# old_control_board.net
KiCad netlist of a schematic drawn in EAGLE
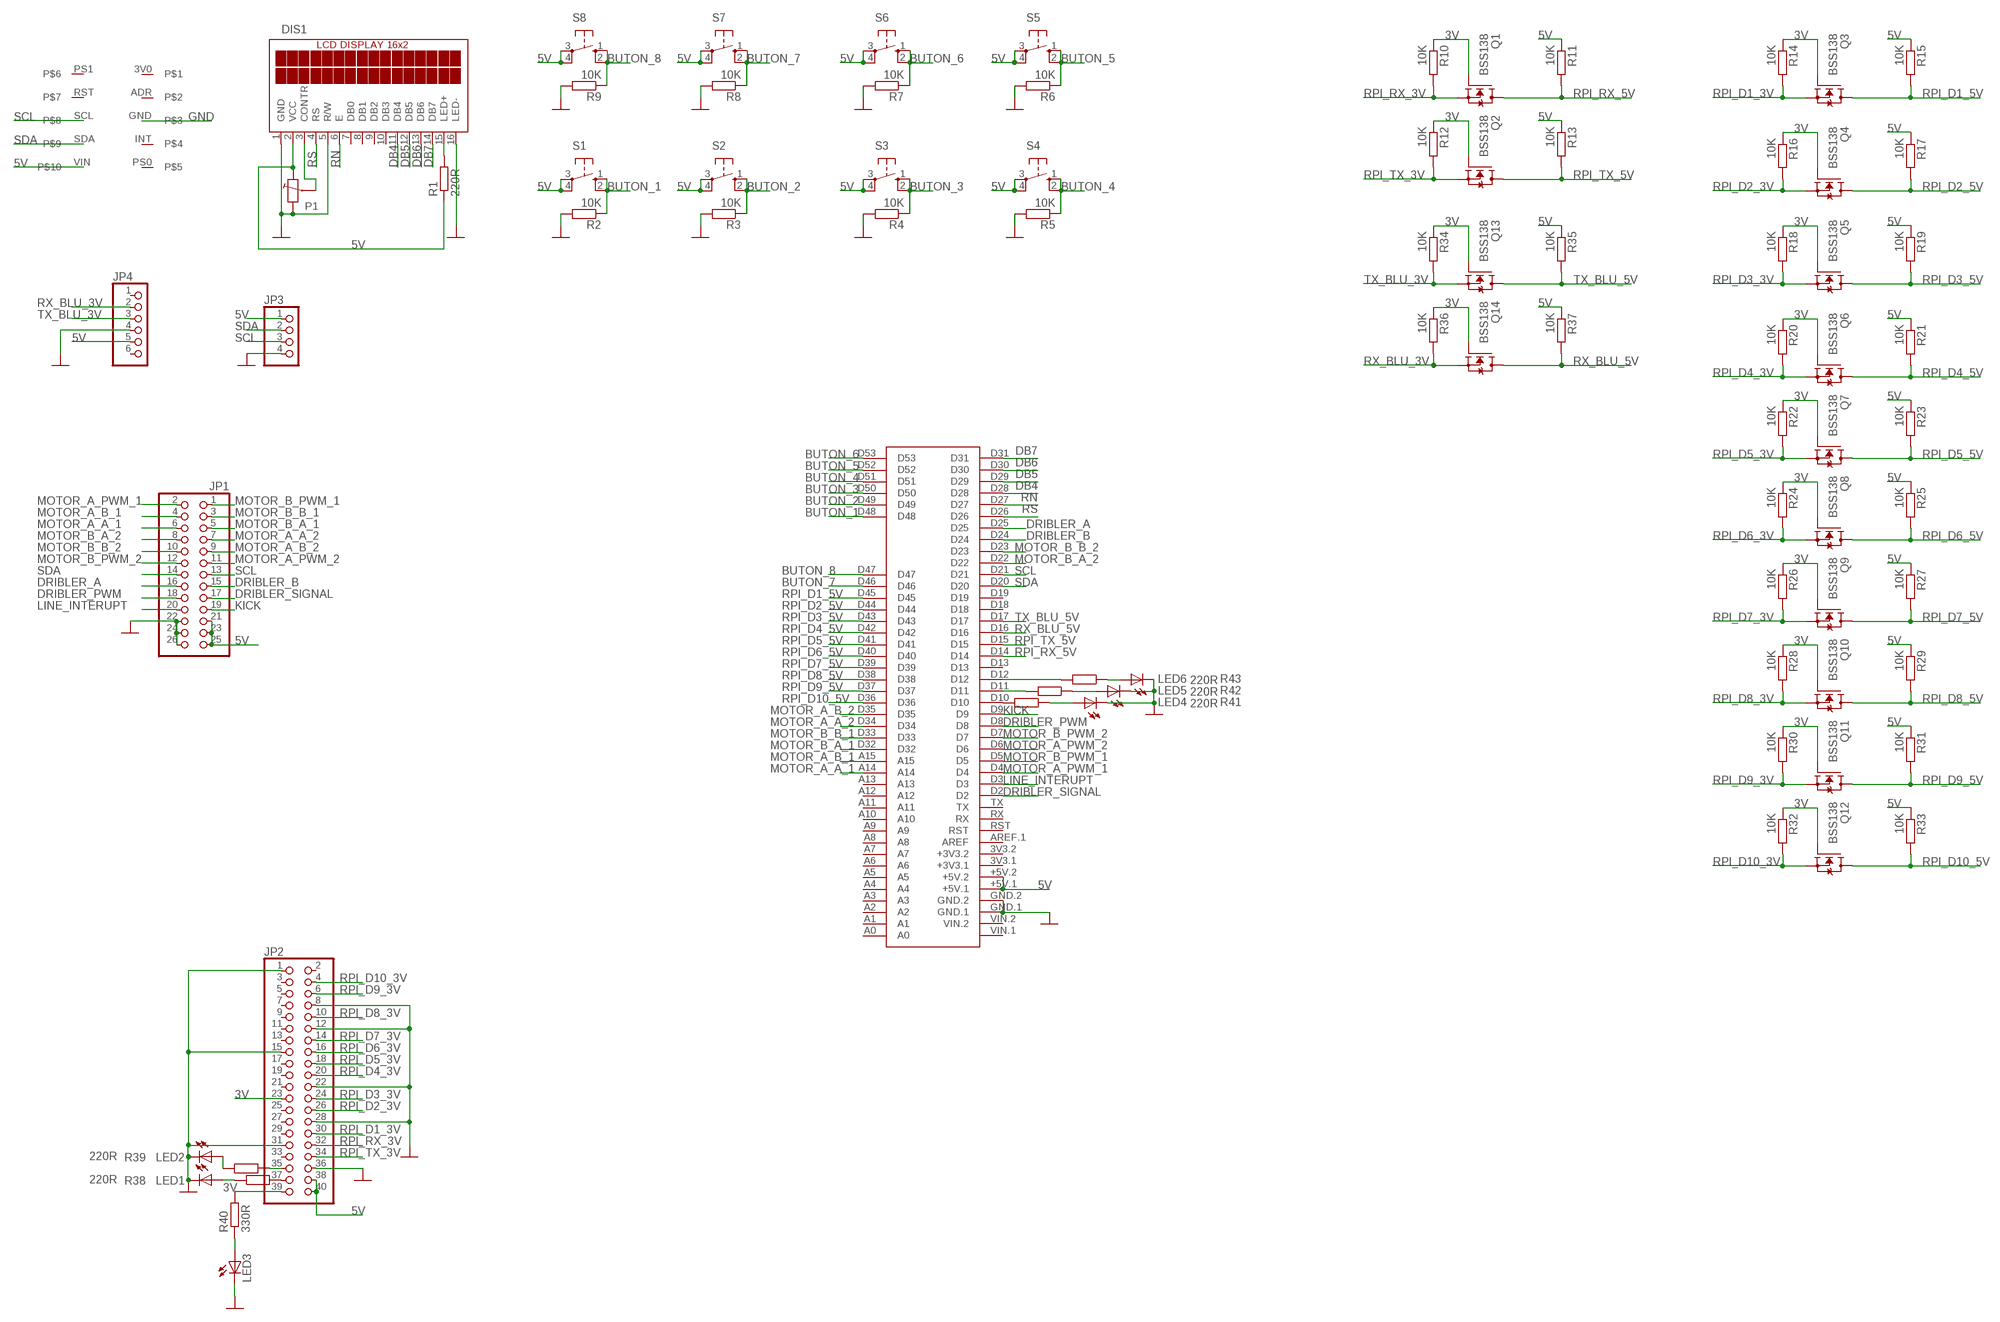
[diagram p0: schematic, sheet 1]

(export (version "E")
  (design (tool "Eeschema 10.0.6"))
  (components
    (comp (ref "DIS1")
      (value "LCD_DISPLEJ_16X2Z")
      (footprint "eagle-import:LCD_DISPLEJ_16X2")
      (libsource (lib "eagle-import") (part "LCD_DISPLEJ_16X2Z"))
    )
    (comp (ref "JP1")
      (value "PINHD-2X13_2.54")
      (footprint "eagle-import:2X13")
      (libsource (lib "eagle-import") (part "PINHD-2X13_2.54"))
    )
    (comp (ref "JP2")
      (value "PINHD-2X20_2.54")
      (footprint "eagle-import:2X20")
      (libsource (lib "eagle-import") (part "PINHD-2X20_2.54"))
    )
    (comp (ref "JP3")
      (value "PINHD-1X4_2.54")
      (footprint "eagle-import:1X04")
      (libsource (lib "eagle-import") (part "PINHD-1X4_2.54"))
    )
    (comp (ref "JP4")
      (value "PINHD-1X6_2.54")
      (footprint "eagle-import:1X06")
      (libsource (lib "eagle-import") (part "PINHD-1X6_2.54"))
    )
    (comp (ref "LED1")
      (value "LEDCHIPLED_0603")
      (footprint "eagle-import:CHIPLED_0603")
      (libsource (lib "eagle-import") (part "LEDCHIPLED_0603"))
    )
    (comp (ref "LED2")
      (value "LEDCHIPLED_0603")
      (footprint "eagle-import:CHIPLED_0603")
      (libsource (lib "eagle-import") (part "LEDCHIPLED_0603"))
    )
    (comp (ref "LED3")
      (value "LEDCHIPLED_0603")
      (footprint "eagle-import:CHIPLED_0603")
      (libsource (lib "eagle-import") (part "LEDCHIPLED_0603"))
    )
    (comp (ref "LED4")
      (value "LEDCHIPLED_0603")
      (footprint "eagle-import:CHIPLED_0603")
      (libsource (lib "eagle-import") (part "LEDCHIPLED_0603"))
    )
    (comp (ref "LED5")
      (value "LEDCHIPLED_0603")
      (footprint "eagle-import:CHIPLED_0603")
      (libsource (lib "eagle-import") (part "LEDCHIPLED_0603"))
    )
    (comp (ref "LED6")
      (value "LEDCHIPLED_0603")
      (footprint "eagle-import:CHIPLED_0603")
      (libsource (lib "eagle-import") (part "LEDCHIPLED_0603"))
    )
    (comp (ref "P1")
      (value "TRIMER-CA6V")
      (footprint "eagle-import:TP-CA6V")
      (libsource (lib "eagle-import") (part "TRIMER-CA6V"))
    )
    (comp (ref "Q1")
      (value "BSS138")
      (footprint "eagle-import:SOT23")
      (fields (field (name "MF") "Fairchild"))
      (libsource (lib "eagle-import") (part "BSS138"))
    )
    (comp (ref "Q2")
      (value "BSS138")
      (footprint "eagle-import:SOT23")
      (fields (field (name "MF") "Fairchild"))
      (libsource (lib "eagle-import") (part "BSS138"))
    )
    (comp (ref "Q3")
      (value "BSS138")
      (footprint "eagle-import:SOT23")
      (fields (field (name "MF") "Fairchild"))
      (libsource (lib "eagle-import") (part "BSS138"))
    )
    (comp (ref "Q4")
      (value "BSS138")
      (footprint "eagle-import:SOT23")
      (fields (field (name "MF") "Fairchild"))
      (libsource (lib "eagle-import") (part "BSS138"))
    )
    (comp (ref "Q5")
      (value "BSS138")
      (footprint "eagle-import:SOT23")
      (fields (field (name "MF") "Fairchild"))
      (libsource (lib "eagle-import") (part "BSS138"))
    )
    (comp (ref "Q6")
      (value "BSS138")
      (footprint "eagle-import:SOT23")
      (fields (field (name "MF") "Fairchild"))
      (libsource (lib "eagle-import") (part "BSS138"))
    )
    (comp (ref "Q7")
      (value "BSS138")
      (footprint "eagle-import:SOT23")
      (fields (field (name "MF") "Fairchild"))
      (libsource (lib "eagle-import") (part "BSS138"))
    )
    (comp (ref "Q8")
      (value "BSS138")
      (footprint "eagle-import:SOT23")
      (fields (field (name "MF") "Fairchild"))
      (libsource (lib "eagle-import") (part "BSS138"))
    )
    (comp (ref "Q9")
      (value "BSS138")
      (footprint "eagle-import:SOT23")
      (fields (field (name "MF") "Fairchild"))
      (libsource (lib "eagle-import") (part "BSS138"))
    )
    (comp (ref "Q10")
      (value "BSS138")
      (footprint "eagle-import:SOT23")
      (fields (field (name "MF") "Fairchild"))
      (libsource (lib "eagle-import") (part "BSS138"))
    )
    (comp (ref "Q11")
      (value "BSS138")
      (footprint "eagle-import:SOT23")
      (fields (field (name "MF") "Fairchild"))
      (libsource (lib "eagle-import") (part "BSS138"))
    )
    (comp (ref "Q12")
      (value "BSS138")
      (footprint "eagle-import:SOT23")
      (fields (field (name "MF") "Fairchild"))
      (libsource (lib "eagle-import") (part "BSS138"))
    )
    (comp (ref "Q13")
      (value "BSS138")
      (footprint "eagle-import:SOT23")
      (fields (field (name "MF") "Fairchild"))
      (libsource (lib "eagle-import") (part "BSS138"))
    )
    (comp (ref "Q14")
      (value "BSS138")
      (footprint "eagle-import:SOT23")
      (fields (field (name "MF") "Fairchild"))
      (libsource (lib "eagle-import") (part "BSS138"))
    )
    (comp (ref "R1")
      (value "220R")
      (footprint "eagle-import:R0603")
      (libsource (lib "eagle-import") (part "R-EU_R0603"))
    )
    (comp (ref "R2")
      (value "10K")
      (footprint "eagle-import:R0603")
      (libsource (lib "eagle-import") (part "R-EU_R0603"))
    )
    (comp (ref "R3")
      (value "10K")
      (footprint "eagle-import:R0603")
      (libsource (lib "eagle-import") (part "R-EU_R0603"))
    )
    (comp (ref "R4")
      (value "10K")
      (footprint "eagle-import:R0603")
      (libsource (lib "eagle-import") (part "R-EU_R0603"))
    )
    (comp (ref "R5")
      (value "10K")
      (footprint "eagle-import:R0603")
      (libsource (lib "eagle-import") (part "R-EU_R0603"))
    )
    (comp (ref "R6")
      (value "10K")
      (footprint "eagle-import:R0603")
      (libsource (lib "eagle-import") (part "R-EU_R0603"))
    )
    (comp (ref "R7")
      (value "10K")
      (footprint "eagle-import:R0603")
      (libsource (lib "eagle-import") (part "R-EU_R0603"))
    )
    (comp (ref "R8")
      (value "10K")
      (footprint "eagle-import:R0603")
      (libsource (lib "eagle-import") (part "R-EU_R0603"))
    )
    (comp (ref "R9")
      (value "10K")
      (footprint "eagle-import:R0603")
      (libsource (lib "eagle-import") (part "R-EU_R0603"))
    )
    (comp (ref "R10")
      (value "10K")
      (footprint "eagle-import:R0603")
      (libsource (lib "eagle-import") (part "R-EU_R0603"))
    )
    (comp (ref "R11")
      (value "10K")
      (footprint "eagle-import:R0603")
      (libsource (lib "eagle-import") (part "R-EU_R0603"))
    )
    (comp (ref "R12")
      (value "10K")
      (footprint "eagle-import:R0603")
      (libsource (lib "eagle-import") (part "R-EU_R0603"))
    )
    (comp (ref "R13")
      (value "10K")
      (footprint "eagle-import:R0603")
      (libsource (lib "eagle-import") (part "R-EU_R0603"))
    )
    (comp (ref "R14")
      (value "10K")
      (footprint "eagle-import:R0603")
      (libsource (lib "eagle-import") (part "R-EU_R0603"))
    )
    (comp (ref "R15")
      (value "10K")
      (footprint "eagle-import:R0603")
      (libsource (lib "eagle-import") (part "R-EU_R0603"))
    )
    (comp (ref "R16")
      (value "10K")
      (footprint "eagle-import:R0603")
      (libsource (lib "eagle-import") (part "R-EU_R0603"))
    )
    (comp (ref "R17")
      (value "10K")
      (footprint "eagle-import:R0603")
      (libsource (lib "eagle-import") (part "R-EU_R0603"))
    )
    (comp (ref "R18")
      (value "10K")
      (footprint "eagle-import:R0603")
      (libsource (lib "eagle-import") (part "R-EU_R0603"))
    )
    (comp (ref "R19")
      (value "10K")
      (footprint "eagle-import:R0603")
      (libsource (lib "eagle-import") (part "R-EU_R0603"))
    )
    (comp (ref "R20")
      (value "10K")
      (footprint "eagle-import:R0603")
      (libsource (lib "eagle-import") (part "R-EU_R0603"))
    )
    (comp (ref "R21")
      (value "10K")
      (footprint "eagle-import:R0603")
      (libsource (lib "eagle-import") (part "R-EU_R0603"))
    )
    (comp (ref "R22")
      (value "10K")
      (footprint "eagle-import:R0603")
      (libsource (lib "eagle-import") (part "R-EU_R0603"))
    )
    (comp (ref "R23")
      (value "10K")
      (footprint "eagle-import:R0603")
      (libsource (lib "eagle-import") (part "R-EU_R0603"))
    )
    (comp (ref "R24")
      (value "10K")
      (footprint "eagle-import:R0603")
      (libsource (lib "eagle-import") (part "R-EU_R0603"))
    )
    (comp (ref "R25")
      (value "10K")
      (footprint "eagle-import:R0603")
      (libsource (lib "eagle-import") (part "R-EU_R0603"))
    )
    (comp (ref "R26")
      (value "10K")
      (footprint "eagle-import:R0603")
      (libsource (lib "eagle-import") (part "R-EU_R0603"))
    )
    (comp (ref "R27")
      (value "10K")
      (footprint "eagle-import:R0603")
      (libsource (lib "eagle-import") (part "R-EU_R0603"))
    )
    (comp (ref "R28")
      (value "10K")
      (footprint "eagle-import:R0603")
      (libsource (lib "eagle-import") (part "R-EU_R0603"))
    )
    (comp (ref "R29")
      (value "10K")
      (footprint "eagle-import:R0603")
      (libsource (lib "eagle-import") (part "R-EU_R0603"))
    )
    (comp (ref "R30")
      (value "10K")
      (footprint "eagle-import:R0603")
      (libsource (lib "eagle-import") (part "R-EU_R0603"))
    )
    (comp (ref "R31")
      (value "10K")
      (footprint "eagle-import:R0603")
      (libsource (lib "eagle-import") (part "R-EU_R0603"))
    )
    (comp (ref "R32")
      (value "10K")
      (footprint "eagle-import:R0603")
      (libsource (lib "eagle-import") (part "R-EU_R0603"))
    )
    (comp (ref "R33")
      (value "10K")
      (footprint "eagle-import:R0603")
      (libsource (lib "eagle-import") (part "R-EU_R0603"))
    )
    (comp (ref "R34")
      (value "10K")
      (footprint "eagle-import:R0603")
      (libsource (lib "eagle-import") (part "R-EU_R0603"))
    )
    (comp (ref "R35")
      (value "10K")
      (footprint "eagle-import:R0603")
      (libsource (lib "eagle-import") (part "R-EU_R0603"))
    )
    (comp (ref "R36")
      (value "10K")
      (footprint "eagle-import:R0603")
      (libsource (lib "eagle-import") (part "R-EU_R0603"))
    )
    (comp (ref "R37")
      (value "10K")
      (footprint "eagle-import:R0603")
      (libsource (lib "eagle-import") (part "R-EU_R0603"))
    )
    (comp (ref "R38")
      (value "220R")
      (footprint "eagle-import:R0603")
      (libsource (lib "eagle-import") (part "R-EU_R0603"))
    )
    (comp (ref "R39")
      (value "220R")
      (footprint "eagle-import:R0603")
      (libsource (lib "eagle-import") (part "R-EU_R0603"))
    )
    (comp (ref "R40")
      (value "330R")
      (footprint "eagle-import:R0603")
      (libsource (lib "eagle-import") (part "R-EU_R0603"))
    )
    (comp (ref "R41")
      (value "220R")
      (footprint "eagle-import:R0603")
      (libsource (lib "eagle-import") (part "R-EU_R0603"))
    )
    (comp (ref "R42")
      (value "220R")
      (footprint "eagle-import:R0603")
      (libsource (lib "eagle-import") (part "R-EU_R0603"))
    )
    (comp (ref "R43")
      (value "220R")
      (footprint "eagle-import:R0603")
      (libsource (lib "eagle-import") (part "R-EU_R0603"))
    )
    (comp (ref "S1")
      (value "10-XX")
      (footprint "eagle-import:B3F-10XX")
      (fields (field (name "MPN") "B3F-1000"))
      (libsource (lib "eagle-import") (part "10-XX"))
    )
    (comp (ref "S2")
      (value "10-XX")
      (footprint "eagle-import:B3F-10XX")
      (fields (field (name "MPN") "B3F-1000"))
      (libsource (lib "eagle-import") (part "10-XX"))
    )
    (comp (ref "S3")
      (value "10-XX")
      (footprint "eagle-import:B3F-10XX")
      (fields (field (name "MPN") "B3F-1000"))
      (libsource (lib "eagle-import") (part "10-XX"))
    )
    (comp (ref "S4")
      (value "10-XX")
      (footprint "eagle-import:B3F-10XX")
      (fields (field (name "MPN") "B3F-1000"))
      (libsource (lib "eagle-import") (part "10-XX"))
    )
    (comp (ref "S5")
      (value "10-XX")
      (footprint "eagle-import:B3F-10XX")
      (fields (field (name "MPN") "B3F-1000"))
      (libsource (lib "eagle-import") (part "10-XX"))
    )
    (comp (ref "S6")
      (value "10-XX")
      (footprint "eagle-import:B3F-10XX")
      (fields (field (name "MPN") "B3F-1000"))
      (libsource (lib "eagle-import") (part "10-XX"))
    )
    (comp (ref "S7")
      (value "10-XX")
      (footprint "eagle-import:B3F-10XX")
      (fields (field (name "MPN") "B3F-1000"))
      (libsource (lib "eagle-import") (part "10-XX"))
    )
    (comp (ref "S8")
      (value "10-XX")
      (footprint "eagle-import:B3F-10XX")
      (fields (field (name "MPN") "B3F-1000"))
      (libsource (lib "eagle-import") (part "10-XX"))
    )
    (comp (ref "U$1")
      (value "MEGA2560_MIKRO")
      (footprint "eagle-import:MEGA2560_MIKRO")
      (libsource (lib "eagle-import") (part "MEGA2560_MIKRO"))
    )
    (comp (ref "U$2")
      (value "BNO055")
      (footprint "eagle-import:BNO005")
      (libsource (lib "eagle-import") (part "BNO055"))
    )
  )
  (nets
    (net (code "1") (name "/3V") (class "Default")
      (node (ref "JP2") (pin "23") (pinfunction "23_23") (pintype "passive"))
      (node (ref "JP2") (pin "39") (pinfunction "39_39") (pintype "passive"))
      (node (ref "Q1") (pin "1") (pinfunction "G_1") (pintype "passive"))
      (node (ref "Q10") (pin "1") (pinfunction "G_1") (pintype "passive"))
      (node (ref "Q11") (pin "1") (pinfunction "G_1") (pintype "passive"))
      (node (ref "Q12") (pin "1") (pinfunction "G_1") (pintype "passive"))
      (node (ref "Q13") (pin "1") (pinfunction "G_1") (pintype "passive"))
      (node (ref "Q14") (pin "1") (pinfunction "G_1") (pintype "passive"))
      (node (ref "Q2") (pin "1") (pinfunction "G_1") (pintype "passive"))
      (node (ref "Q3") (pin "1") (pinfunction "G_1") (pintype "passive"))
      (node (ref "Q4") (pin "1") (pinfunction "G_1") (pintype "passive"))
      (node (ref "Q5") (pin "1") (pinfunction "G_1") (pintype "passive"))
      (node (ref "Q6") (pin "1") (pinfunction "G_1") (pintype "passive"))
      (node (ref "Q7") (pin "1") (pinfunction "G_1") (pintype "passive"))
      (node (ref "Q8") (pin "1") (pinfunction "G_1") (pintype "passive"))
      (node (ref "Q9") (pin "1") (pinfunction "G_1") (pintype "passive"))
      (node (ref "R10") (pin "1") (pinfunction "1_1") (pintype "passive"))
      (node (ref "R12") (pin "1") (pinfunction "1_1") (pintype "passive"))
      (node (ref "R14") (pin "1") (pinfunction "1_1") (pintype "passive"))
      (node (ref "R16") (pin "1") (pinfunction "1_1") (pintype "passive"))
      (node (ref "R18") (pin "1") (pinfunction "1_1") (pintype "passive"))
      (node (ref "R20") (pin "1") (pinfunction "1_1") (pintype "passive"))
      (node (ref "R22") (pin "1") (pinfunction "1_1") (pintype "passive"))
      (node (ref "R24") (pin "1") (pinfunction "1_1") (pintype "passive"))
      (node (ref "R26") (pin "1") (pinfunction "1_1") (pintype "passive"))
      (node (ref "R28") (pin "1") (pinfunction "1_1") (pintype "passive"))
      (node (ref "R30") (pin "1") (pinfunction "1_1") (pintype "passive"))
      (node (ref "R32") (pin "1") (pinfunction "1_1") (pintype "passive"))
      (node (ref "R34") (pin "1") (pinfunction "1_1") (pintype "passive"))
      (node (ref "R36") (pin "1") (pinfunction "1_1") (pintype "passive"))
      (node (ref "R40") (pin "2") (pinfunction "2_2") (pintype "passive"))
    )
    (net (code "2") (name "/5V") (class "Default")
      (node (ref "DIS1") (pin "2") (pinfunction "VCC_2") (pintype "power_in"))
      (node (ref "JP1") (pin "21") (pinfunction "21_21") (pintype "passive"))
      (node (ref "JP1") (pin "23") (pinfunction "23_23") (pintype "passive"))
      (node (ref "JP1") (pin "25") (pinfunction "25_25") (pintype "passive"))
      (node (ref "JP2") (pin "38") (pinfunction "38_38") (pintype "passive"))
      (node (ref "JP2") (pin "40") (pinfunction "40_40") (pintype "passive"))
      (node (ref "JP3") (pin "1") (pinfunction "1_1") (pintype "passive"))
      (node (ref "JP4") (pin "5") (pinfunction "5_5") (pintype "passive"))
      (node (ref "P1") (pin "2") (pinfunction "2_2") (pintype "passive"))
      (node (ref "R1") (pin "1") (pinfunction "1_1") (pintype "passive"))
      (node (ref "R11") (pin "1") (pinfunction "1_1") (pintype "passive"))
      (node (ref "R13") (pin "1") (pinfunction "1_1") (pintype "passive"))
      (node (ref "R15") (pin "1") (pinfunction "1_1") (pintype "passive"))
      (node (ref "R17") (pin "1") (pinfunction "1_1") (pintype "passive"))
      (node (ref "R19") (pin "1") (pinfunction "1_1") (pintype "passive"))
      (node (ref "R21") (pin "1") (pinfunction "1_1") (pintype "passive"))
      (node (ref "R23") (pin "1") (pinfunction "1_1") (pintype "passive"))
      (node (ref "R25") (pin "1") (pinfunction "1_1") (pintype "passive"))
      (node (ref "R27") (pin "1") (pinfunction "1_1") (pintype "passive"))
      (node (ref "R29") (pin "1") (pinfunction "1_1") (pintype "passive"))
      (node (ref "R31") (pin "1") (pinfunction "1_1") (pintype "passive"))
      (node (ref "R33") (pin "1") (pinfunction "1_1") (pintype "passive"))
      (node (ref "R35") (pin "1") (pinfunction "1_1") (pintype "passive"))
      (node (ref "R37") (pin "1") (pinfunction "1_1") (pintype "passive"))
      (node (ref "S1") (pin "3") (pinfunction "P_3") (pintype "passive"))
      (node (ref "S1") (pin "4") (pinfunction "P1_4") (pintype "passive"))
      (node (ref "S2") (pin "3") (pinfunction "P_3") (pintype "passive"))
      (node (ref "S2") (pin "4") (pinfunction "P1_4") (pintype "passive"))
      (node (ref "S3") (pin "3") (pinfunction "P_3") (pintype "passive"))
      (node (ref "S3") (pin "4") (pinfunction "P1_4") (pintype "passive"))
      (node (ref "S4") (pin "3") (pinfunction "P_3") (pintype "passive"))
      (node (ref "S4") (pin "4") (pinfunction "P1_4") (pintype "passive"))
      (node (ref "S5") (pin "3") (pinfunction "P_3") (pintype "passive"))
      (node (ref "S5") (pin "4") (pinfunction "P1_4") (pintype "passive"))
      (node (ref "S6") (pin "3") (pinfunction "P_3") (pintype "passive"))
      (node (ref "S6") (pin "4") (pinfunction "P1_4") (pintype "passive"))
      (node (ref "S7") (pin "3") (pinfunction "P_3") (pintype "passive"))
      (node (ref "S7") (pin "4") (pinfunction "P1_4") (pintype "passive"))
      (node (ref "S8") (pin "3") (pinfunction "P_3") (pintype "passive"))
      (node (ref "S8") (pin "4") (pinfunction "P1_4") (pintype "passive"))
      (node (ref "U$1") (pin "+5V.1") (pinfunction "+5V.1_+5V.1") (pintype "bidirectional"))
      (node (ref "U$1") (pin "+5V.2") (pinfunction "+5V.2_+5V.2") (pintype "bidirectional"))
      (node (ref "U$2") (pin "VIN") (pinfunction "P$10_VIN") (pintype "bidirectional"))
    )
    (net (code "3") (name "/BUTON_1") (class "Default")
      (node (ref "R2") (pin "1") (pinfunction "1_1") (pintype "passive"))
      (node (ref "S1") (pin "1") (pinfunction "S_1") (pintype "passive"))
      (node (ref "S1") (pin "2") (pinfunction "S1_2") (pintype "passive"))
      (node (ref "U$1") (pin "D48") (pinfunction "D48_D48") (pintype "bidirectional"))
    )
    (net (code "4") (name "/BUTON_2") (class "Default")
      (node (ref "R3") (pin "1") (pinfunction "1_1") (pintype "passive"))
      (node (ref "S2") (pin "1") (pinfunction "S_1") (pintype "passive"))
      (node (ref "S2") (pin "2") (pinfunction "S1_2") (pintype "passive"))
      (node (ref "U$1") (pin "D49") (pinfunction "D49_D49") (pintype "bidirectional"))
    )
    (net (code "5") (name "/BUTON_3") (class "Default")
      (node (ref "R4") (pin "1") (pinfunction "1_1") (pintype "passive"))
      (node (ref "S3") (pin "1") (pinfunction "S_1") (pintype "passive"))
      (node (ref "S3") (pin "2") (pinfunction "S1_2") (pintype "passive"))
      (node (ref "U$1") (pin "D50") (pinfunction "D50_D50") (pintype "bidirectional"))
    )
    (net (code "6") (name "/BUTON_4") (class "Default")
      (node (ref "R5") (pin "1") (pinfunction "1_1") (pintype "passive"))
      (node (ref "S4") (pin "1") (pinfunction "S_1") (pintype "passive"))
      (node (ref "S4") (pin "2") (pinfunction "S1_2") (pintype "passive"))
      (node (ref "U$1") (pin "D51") (pinfunction "D51_D51") (pintype "bidirectional"))
    )
    (net (code "7") (name "/BUTON_5") (class "Default")
      (node (ref "R6") (pin "1") (pinfunction "1_1") (pintype "passive"))
      (node (ref "S5") (pin "1") (pinfunction "S_1") (pintype "passive"))
      (node (ref "S5") (pin "2") (pinfunction "S1_2") (pintype "passive"))
      (node (ref "U$1") (pin "D52") (pinfunction "D52_D52") (pintype "bidirectional"))
    )
    (net (code "8") (name "/BUTON_6") (class "Default")
      (node (ref "R7") (pin "1") (pinfunction "1_1") (pintype "passive"))
      (node (ref "S6") (pin "1") (pinfunction "S_1") (pintype "passive"))
      (node (ref "S6") (pin "2") (pinfunction "S1_2") (pintype "passive"))
      (node (ref "U$1") (pin "D53") (pinfunction "D53_D53") (pintype "bidirectional"))
    )
    (net (code "9") (name "/BUTON_7") (class "Default")
      (node (ref "R8") (pin "1") (pinfunction "1_1") (pintype "passive"))
      (node (ref "S7") (pin "1") (pinfunction "S_1") (pintype "passive"))
      (node (ref "S7") (pin "2") (pinfunction "S1_2") (pintype "passive"))
      (node (ref "U$1") (pin "D46") (pinfunction "D46_D46") (pintype "bidirectional"))
    )
    (net (code "10") (name "/BUTON_8") (class "Default")
      (node (ref "R9") (pin "1") (pinfunction "1_1") (pintype "passive"))
      (node (ref "S8") (pin "1") (pinfunction "S_1") (pintype "passive"))
      (node (ref "S8") (pin "2") (pinfunction "S1_2") (pintype "passive"))
      (node (ref "U$1") (pin "D47") (pinfunction "D47_D47") (pintype "bidirectional"))
    )
    (net (code "11") (name "/DB4") (class "Default")
      (node (ref "DIS1") (pin "11") (pinfunction "DB4_11") (pintype "bidirectional"))
      (node (ref "U$1") (pin "D28") (pinfunction "D28_D28") (pintype "bidirectional"))
    )
    (net (code "12") (name "/DB5") (class "Default")
      (node (ref "DIS1") (pin "12") (pinfunction "DB5_12") (pintype "bidirectional"))
      (node (ref "U$1") (pin "D29") (pinfunction "D29_D29") (pintype "bidirectional"))
    )
    (net (code "13") (name "/DB6") (class "Default")
      (node (ref "DIS1") (pin "13") (pinfunction "DB6_13") (pintype "bidirectional"))
      (node (ref "U$1") (pin "D30") (pinfunction "D30_D30") (pintype "bidirectional"))
    )
    (net (code "14") (name "/DB7") (class "Default")
      (node (ref "DIS1") (pin "14") (pinfunction "DB7_14") (pintype "bidirectional"))
      (node (ref "U$1") (pin "D31") (pinfunction "D31_D31") (pintype "bidirectional"))
    )
    (net (code "15") (name "/DRIBLER_A") (class "Default")
      (node (ref "JP1") (pin "16") (pinfunction "16_16") (pintype "passive"))
      (node (ref "U$1") (pin "D25") (pinfunction "D25_D25") (pintype "bidirectional"))
    )
    (net (code "16") (name "/DRIBLER_B") (class "Default")
      (node (ref "JP1") (pin "15") (pinfunction "15_15") (pintype "passive"))
      (node (ref "U$1") (pin "D24") (pinfunction "D24_D24") (pintype "bidirectional"))
    )
    (net (code "17") (name "/DRIBLER_PWM") (class "Default")
      (node (ref "JP1") (pin "18") (pinfunction "18_18") (pintype "passive"))
      (node (ref "U$1") (pin "D8") (pinfunction "D8_D8") (pintype "bidirectional"))
    )
    (net (code "18") (name "/DRIBLER_SIGNAL") (class "Default")
      (node (ref "JP1") (pin "17") (pinfunction "17_17") (pintype "passive"))
      (node (ref "U$1") (pin "D2") (pinfunction "D2_D2") (pintype "bidirectional"))
    )
    (net (code "19") (name "/KICK") (class "Default")
      (node (ref "JP1") (pin "19") (pinfunction "19_19") (pintype "passive"))
      (node (ref "U$1") (pin "D9") (pinfunction "D9_D9") (pintype "bidirectional"))
    )
    (net (code "20") (name "/LINE_INTERUPT") (class "Default")
      (node (ref "JP1") (pin "20") (pinfunction "20_20") (pintype "passive"))
      (node (ref "U$1") (pin "D3") (pinfunction "D3_D3") (pintype "bidirectional"))
    )
    (net (code "21") (name "/MOTOR_A_A_1") (class "Default")
      (node (ref "JP1") (pin "6") (pinfunction "6_6") (pintype "passive"))
      (node (ref "U$1") (pin "A14") (pinfunction "A14_A14") (pintype "bidirectional"))
    )
    (net (code "22") (name "/MOTOR_A_A_2") (class "Default")
      (node (ref "JP1") (pin "7") (pinfunction "7_7") (pintype "passive"))
      (node (ref "U$1") (pin "D34") (pinfunction "D34_D34") (pintype "bidirectional"))
    )
    (net (code "23") (name "/MOTOR_A_B_1") (class "Default")
      (node (ref "JP1") (pin "4") (pinfunction "4_4") (pintype "passive"))
      (node (ref "U$1") (pin "A15") (pinfunction "A15_A15") (pintype "bidirectional"))
    )
    (net (code "24") (name "/MOTOR_A_B_2") (class "Default")
      (node (ref "JP1") (pin "9") (pinfunction "9_9") (pintype "passive"))
      (node (ref "U$1") (pin "D35") (pinfunction "D35_D35") (pintype "bidirectional"))
    )
    (net (code "25") (name "/MOTOR_A_PWM_1") (class "Default")
      (node (ref "JP1") (pin "2") (pinfunction "2_2") (pintype "passive"))
      (node (ref "U$1") (pin "D4") (pinfunction "D4_D4") (pintype "bidirectional"))
    )
    (net (code "26") (name "/MOTOR_A_PWM_2") (class "Default")
      (node (ref "JP1") (pin "11") (pinfunction "11_11") (pintype "passive"))
      (node (ref "U$1") (pin "D6") (pinfunction "D6_D6") (pintype "bidirectional"))
    )
    (net (code "27") (name "/MOTOR_B_A_1") (class "Default")
      (node (ref "JP1") (pin "5") (pinfunction "5_5") (pintype "passive"))
      (node (ref "U$1") (pin "D32") (pinfunction "D32_D32") (pintype "bidirectional"))
    )
    (net (code "28") (name "/MOTOR_B_A_2") (class "Default")
      (node (ref "JP1") (pin "8") (pinfunction "8_8") (pintype "passive"))
      (node (ref "U$1") (pin "D22") (pinfunction "D22_D22") (pintype "bidirectional"))
    )
    (net (code "29") (name "/MOTOR_B_B_1") (class "Default")
      (node (ref "JP1") (pin "3") (pinfunction "3_3") (pintype "passive"))
      (node (ref "U$1") (pin "D33") (pinfunction "D33_D33") (pintype "bidirectional"))
    )
    (net (code "30") (name "/MOTOR_B_B_2") (class "Default")
      (node (ref "JP1") (pin "10") (pinfunction "10_10") (pintype "passive"))
      (node (ref "U$1") (pin "D23") (pinfunction "D23_D23") (pintype "bidirectional"))
    )
    (net (code "31") (name "/MOTOR_B_PWM_1") (class "Default")
      (node (ref "JP1") (pin "1") (pinfunction "1_1") (pintype "passive"))
      (node (ref "U$1") (pin "D5") (pinfunction "D5_D5") (pintype "bidirectional"))
    )
    (net (code "32") (name "/MOTOR_B_PWM_2") (class "Default")
      (node (ref "JP1") (pin "12") (pinfunction "12_12") (pintype "passive"))
      (node (ref "U$1") (pin "D7") (pinfunction "D7_D7") (pintype "bidirectional"))
    )
    (net (code "33") (name "/RN") (class "Default")
      (node (ref "DIS1") (pin "6") (pinfunction "E_6") (pintype "input"))
      (node (ref "U$1") (pin "D27") (pinfunction "D27_D27") (pintype "bidirectional"))
    )
    (net (code "34") (name "/RPI_D1_3V") (class "Default")
      (node (ref "JP2") (pin "30") (pinfunction "30_30") (pintype "passive"))
      (node (ref "Q3") (pin "2") (pinfunction "S_2") (pintype "passive"))
      (node (ref "R14") (pin "2") (pinfunction "2_2") (pintype "passive"))
    )
    (net (code "35") (name "/RPI_D1_5V") (class "Default")
      (node (ref "Q3") (pin "3") (pinfunction "D_3") (pintype "passive"))
      (node (ref "R15") (pin "2") (pinfunction "2_2") (pintype "passive"))
      (node (ref "U$1") (pin "D45") (pinfunction "D45_D45") (pintype "bidirectional"))
    )
    (net (code "36") (name "/RPI_D2_3V") (class "Default")
      (node (ref "JP2") (pin "26") (pinfunction "26_26") (pintype "passive"))
      (node (ref "Q4") (pin "2") (pinfunction "S_2") (pintype "passive"))
      (node (ref "R16") (pin "2") (pinfunction "2_2") (pintype "passive"))
    )
    (net (code "37") (name "/RPI_D2_5V") (class "Default")
      (node (ref "Q4") (pin "3") (pinfunction "D_3") (pintype "passive"))
      (node (ref "R17") (pin "2") (pinfunction "2_2") (pintype "passive"))
      (node (ref "U$1") (pin "D44") (pinfunction "D44_D44") (pintype "bidirectional"))
    )
    (net (code "38") (name "/RPI_D3_3V") (class "Default")
      (node (ref "JP2") (pin "24") (pinfunction "24_24") (pintype "passive"))
      (node (ref "Q5") (pin "2") (pinfunction "S_2") (pintype "passive"))
      (node (ref "R18") (pin "2") (pinfunction "2_2") (pintype "passive"))
    )
    (net (code "39") (name "/RPI_D3_5V") (class "Default")
      (node (ref "Q5") (pin "3") (pinfunction "D_3") (pintype "passive"))
      (node (ref "R19") (pin "2") (pinfunction "2_2") (pintype "passive"))
      (node (ref "U$1") (pin "D43") (pinfunction "D43_D43") (pintype "bidirectional"))
    )
    (net (code "40") (name "/RPI_D4_3V") (class "Default")
      (node (ref "JP2") (pin "20") (pinfunction "20_20") (pintype "passive"))
      (node (ref "Q6") (pin "2") (pinfunction "S_2") (pintype "passive"))
      (node (ref "R20") (pin "2") (pinfunction "2_2") (pintype "passive"))
    )
    (net (code "41") (name "/RPI_D4_5V") (class "Default")
      (node (ref "Q6") (pin "3") (pinfunction "D_3") (pintype "passive"))
      (node (ref "R21") (pin "2") (pinfunction "2_2") (pintype "passive"))
      (node (ref "U$1") (pin "D42") (pinfunction "D42_D42") (pintype "bidirectional"))
    )
    (net (code "42") (name "/RPI_D5_3V") (class "Default")
      (node (ref "JP2") (pin "18") (pinfunction "18_18") (pintype "passive"))
      (node (ref "Q7") (pin "2") (pinfunction "S_2") (pintype "passive"))
      (node (ref "R22") (pin "2") (pinfunction "2_2") (pintype "passive"))
    )
    (net (code "43") (name "/RPI_D5_5V") (class "Default")
      (node (ref "Q7") (pin "3") (pinfunction "D_3") (pintype "passive"))
      (node (ref "R23") (pin "2") (pinfunction "2_2") (pintype "passive"))
      (node (ref "U$1") (pin "D41") (pinfunction "D41_D41") (pintype "bidirectional"))
    )
    (net (code "44") (name "/RPI_D6_3V") (class "Default")
      (node (ref "JP2") (pin "16") (pinfunction "16_16") (pintype "passive"))
      (node (ref "Q8") (pin "2") (pinfunction "S_2") (pintype "passive"))
      (node (ref "R24") (pin "2") (pinfunction "2_2") (pintype "passive"))
    )
    (net (code "45") (name "/RPI_D6_5V") (class "Default")
      (node (ref "Q8") (pin "3") (pinfunction "D_3") (pintype "passive"))
      (node (ref "R25") (pin "2") (pinfunction "2_2") (pintype "passive"))
      (node (ref "U$1") (pin "D40") (pinfunction "D40_D40") (pintype "bidirectional"))
    )
    (net (code "46") (name "/RPI_D7_3V") (class "Default")
      (node (ref "JP2") (pin "14") (pinfunction "14_14") (pintype "passive"))
      (node (ref "Q9") (pin "2") (pinfunction "S_2") (pintype "passive"))
      (node (ref "R26") (pin "2") (pinfunction "2_2") (pintype "passive"))
    )
    (net (code "47") (name "/RPI_D7_5V") (class "Default")
      (node (ref "Q9") (pin "3") (pinfunction "D_3") (pintype "passive"))
      (node (ref "R27") (pin "2") (pinfunction "2_2") (pintype "passive"))
      (node (ref "U$1") (pin "D39") (pinfunction "D39_D39") (pintype "bidirectional"))
    )
    (net (code "48") (name "/RPI_D8_3V") (class "Default")
      (node (ref "JP2") (pin "10") (pinfunction "10_10") (pintype "passive"))
      (node (ref "Q10") (pin "2") (pinfunction "S_2") (pintype "passive"))
      (node (ref "R28") (pin "2") (pinfunction "2_2") (pintype "passive"))
    )
    (net (code "49") (name "/RPI_D8_5V") (class "Default")
      (node (ref "Q10") (pin "3") (pinfunction "D_3") (pintype "passive"))
      (node (ref "R29") (pin "2") (pinfunction "2_2") (pintype "passive"))
      (node (ref "U$1") (pin "D38") (pinfunction "D38_D38") (pintype "bidirectional"))
    )
    (net (code "50") (name "/RPI_D9_3V") (class "Default")
      (node (ref "JP2") (pin "6") (pinfunction "6_6") (pintype "passive"))
      (node (ref "Q11") (pin "2") (pinfunction "S_2") (pintype "passive"))
      (node (ref "R30") (pin "2") (pinfunction "2_2") (pintype "passive"))
    )
    (net (code "51") (name "/RPI_D9_5V") (class "Default")
      (node (ref "Q11") (pin "3") (pinfunction "D_3") (pintype "passive"))
      (node (ref "R31") (pin "2") (pinfunction "2_2") (pintype "passive"))
      (node (ref "U$1") (pin "D37") (pinfunction "D37_D37") (pintype "bidirectional"))
    )
    (net (code "52") (name "/RPI_D10_3V") (class "Default")
      (node (ref "JP2") (pin "4") (pinfunction "4_4") (pintype "passive"))
      (node (ref "Q12") (pin "2") (pinfunction "S_2") (pintype "passive"))
      (node (ref "R32") (pin "2") (pinfunction "2_2") (pintype "passive"))
    )
    (net (code "53") (name "/RPI_D10_5V") (class "Default")
      (node (ref "Q12") (pin "3") (pinfunction "D_3") (pintype "passive"))
      (node (ref "R33") (pin "2") (pinfunction "2_2") (pintype "passive"))
      (node (ref "U$1") (pin "D36") (pinfunction "D36_D36") (pintype "bidirectional"))
    )
    (net (code "54") (name "/RPI_RX_3V") (class "Default")
      (node (ref "JP2") (pin "32") (pinfunction "32_32") (pintype "passive"))
      (node (ref "Q1") (pin "2") (pinfunction "S_2") (pintype "passive"))
      (node (ref "R10") (pin "2") (pinfunction "2_2") (pintype "passive"))
    )
    (net (code "55") (name "/RPI_RX_5V") (class "Default")
      (node (ref "Q1") (pin "3") (pinfunction "D_3") (pintype "passive"))
      (node (ref "R11") (pin "2") (pinfunction "2_2") (pintype "passive"))
      (node (ref "U$1") (pin "D14") (pinfunction "D14_D14") (pintype "bidirectional"))
    )
    (net (code "56") (name "/RPI_TX_3V") (class "Default")
      (node (ref "JP2") (pin "34") (pinfunction "34_34") (pintype "passive"))
      (node (ref "Q2") (pin "2") (pinfunction "S_2") (pintype "passive"))
      (node (ref "R12") (pin "2") (pinfunction "2_2") (pintype "passive"))
    )
    (net (code "57") (name "/RPI_TX_5V") (class "Default")
      (node (ref "Q2") (pin "3") (pinfunction "D_3") (pintype "passive"))
      (node (ref "R13") (pin "2") (pinfunction "2_2") (pintype "passive"))
      (node (ref "U$1") (pin "D15") (pinfunction "D15_D15") (pintype "bidirectional"))
    )
    (net (code "58") (name "/RS") (class "Default")
      (node (ref "DIS1") (pin "4") (pinfunction "RS_4") (pintype "input"))
      (node (ref "U$1") (pin "D26") (pinfunction "D26_D26") (pintype "bidirectional"))
    )
    (net (code "59") (name "/RX_BLU_3V") (class "Default")
      (node (ref "JP4") (pin "2") (pinfunction "2_2") (pintype "passive"))
      (node (ref "Q14") (pin "2") (pinfunction "S_2") (pintype "passive"))
      (node (ref "R36") (pin "2") (pinfunction "2_2") (pintype "passive"))
    )
    (net (code "60") (name "/RX_BLU_5V") (class "Default")
      (node (ref "Q14") (pin "3") (pinfunction "D_3") (pintype "passive"))
      (node (ref "R37") (pin "2") (pinfunction "2_2") (pintype "passive"))
      (node (ref "U$1") (pin "D16") (pinfunction "D16_D16") (pintype "bidirectional"))
    )
    (net (code "61") (name "/SCL") (class "Default")
      (node (ref "JP1") (pin "13") (pinfunction "13_13") (pintype "passive"))
      (node (ref "JP3") (pin "3") (pinfunction "3_3") (pintype "passive"))
      (node (ref "U$1") (pin "D21") (pinfunction "D21_D21") (pintype "bidirectional"))
      (node (ref "U$2") (pin "SCL") (pinfunction "P$8_SCL") (pintype "bidirectional"))
    )
    (net (code "62") (name "/SDA") (class "Default")
      (node (ref "JP1") (pin "14") (pinfunction "14_14") (pintype "passive"))
      (node (ref "JP3") (pin "2") (pinfunction "2_2") (pintype "passive"))
      (node (ref "U$1") (pin "D20") (pinfunction "D20_D20") (pintype "bidirectional"))
      (node (ref "U$2") (pin "SDA") (pinfunction "P$9_SDA") (pintype "bidirectional"))
    )
    (net (code "63") (name "/TX_BLU_3V") (class "Default")
      (node (ref "JP4") (pin "3") (pinfunction "3_3") (pintype "passive"))
      (node (ref "Q13") (pin "2") (pinfunction "S_2") (pintype "passive"))
      (node (ref "R34") (pin "2") (pinfunction "2_2") (pintype "passive"))
    )
    (net (code "64") (name "/TX_BLU_5V") (class "Default")
      (node (ref "Q13") (pin "3") (pinfunction "D_3") (pintype "passive"))
      (node (ref "R35") (pin "2") (pinfunction "2_2") (pintype "passive"))
      (node (ref "U$1") (pin "D17") (pinfunction "D17_D17") (pintype "bidirectional"))
    )
    (net (code "65") (name "GND") (class "Default")
      (node (ref "DIS1") (pin "1") (pinfunction "GND_1") (pintype "power_in"))
      (node (ref "DIS1") (pin "16") (pinfunction "LED-_16") (pintype "passive"))
      (node (ref "DIS1") (pin "5") (pinfunction "R/W_5") (pintype "input"))
      (node (ref "JP1") (pin "22") (pinfunction "22_22") (pintype "passive"))
      (node (ref "JP1") (pin "24") (pinfunction "24_24") (pintype "passive"))
      (node (ref "JP1") (pin "26") (pinfunction "26_26") (pintype "passive"))
      (node (ref "JP2") (pin "1") (pinfunction "1_1") (pintype "passive"))
      (node (ref "JP2") (pin "12") (pinfunction "12_12") (pintype "passive"))
      (node (ref "JP2") (pin "15") (pinfunction "15_15") (pintype "passive"))
      (node (ref "JP2") (pin "22") (pinfunction "22_22") (pintype "passive"))
      (node (ref "JP2") (pin "28") (pinfunction "28_28") (pintype "passive"))
      (node (ref "JP2") (pin "31") (pinfunction "31_31") (pintype "passive"))
      (node (ref "JP2") (pin "36") (pinfunction "36_36") (pintype "passive"))
      (node (ref "JP2") (pin "8") (pinfunction "8_8") (pintype "passive"))
      (node (ref "JP3") (pin "4") (pinfunction "4_4") (pintype "passive"))
      (node (ref "JP4") (pin "4") (pinfunction "4_4") (pintype "passive"))
      (node (ref "LED1") (pin "C") (pinfunction "C_C") (pintype "passive"))
      (node (ref "LED2") (pin "C") (pinfunction "C_C") (pintype "passive"))
      (node (ref "LED3") (pin "C") (pinfunction "C_C") (pintype "passive"))
      (node (ref "LED4") (pin "C") (pinfunction "C_C") (pintype "passive"))
      (node (ref "LED5") (pin "C") (pinfunction "C_C") (pintype "passive"))
      (node (ref "LED6") (pin "C") (pinfunction "C_C") (pintype "passive"))
      (node (ref "P1") (pin "1") (pinfunction "1_1") (pintype "passive"))
      (node (ref "R2") (pin "2") (pinfunction "2_2") (pintype "passive"))
      (node (ref "R3") (pin "2") (pinfunction "2_2") (pintype "passive"))
      (node (ref "R4") (pin "2") (pinfunction "2_2") (pintype "passive"))
      (node (ref "R5") (pin "2") (pinfunction "2_2") (pintype "passive"))
      (node (ref "R6") (pin "2") (pinfunction "2_2") (pintype "passive"))
      (node (ref "R7") (pin "2") (pinfunction "2_2") (pintype "passive"))
      (node (ref "R8") (pin "2") (pinfunction "2_2") (pintype "passive"))
      (node (ref "R9") (pin "2") (pinfunction "2_2") (pintype "passive"))
      (node (ref "U$1") (pin "GND.1") (pinfunction "GND.1_GND.1") (pintype "bidirectional"))
      (node (ref "U$1") (pin "GND.2") (pinfunction "GND.2_GND.2") (pintype "bidirectional"))
      (node (ref "U$2") (pin "GND") (pinfunction "P$3_GND") (pintype "bidirectional"))
    )
    (net (code "66") (name "Net-(DIS1-CONTR)") (class "Default")
      (node (ref "DIS1") (pin "3") (pinfunction "CONTR_3") (pintype "input"))
      (node (ref "P1") (pin "BEZ") (pinfunction "BEZ_BEZ") (pintype "passive"))
    )
    (net (code "67") (name "Net-(DIS1-LED+)") (class "Default")
      (node (ref "DIS1") (pin "15") (pinfunction "LED+_15") (pintype "passive"))
      (node (ref "R1") (pin "2") (pinfunction "2_2") (pintype "passive"))
    )
    (net (code "68") (name "Net-(JP2-Pad35)") (class "Default")
      (node (ref "JP2") (pin "35") (pinfunction "35_35") (pintype "passive"))
      (node (ref "R39") (pin "2") (pinfunction "2_2") (pintype "passive"))
    )
    (net (code "69") (name "Net-(JP2-Pad37)") (class "Default")
      (node (ref "JP2") (pin "37") (pinfunction "37_37") (pintype "passive"))
      (node (ref "R38") (pin "2") (pinfunction "2_2") (pintype "passive"))
    )
    (net (code "70") (name "Net-(LED1-PadA)") (class "Default")
      (node (ref "LED1") (pin "A") (pinfunction "A_A") (pintype "passive"))
      (node (ref "R38") (pin "1") (pinfunction "1_1") (pintype "passive"))
    )
    (net (code "71") (name "Net-(LED2-PadA)") (class "Default")
      (node (ref "LED2") (pin "A") (pinfunction "A_A") (pintype "passive"))
      (node (ref "R39") (pin "1") (pinfunction "1_1") (pintype "passive"))
    )
    (net (code "72") (name "Net-(LED3-PadA)") (class "Default")
      (node (ref "LED3") (pin "A") (pinfunction "A_A") (pintype "passive"))
      (node (ref "R40") (pin "1") (pinfunction "1_1") (pintype "passive"))
    )
    (net (code "73") (name "Net-(LED4-PadA)") (class "Default")
      (node (ref "LED4") (pin "A") (pinfunction "A_A") (pintype "passive"))
      (node (ref "R41") (pin "1") (pinfunction "1_1") (pintype "passive"))
    )
    (net (code "74") (name "Net-(LED5-PadA)") (class "Default")
      (node (ref "LED5") (pin "A") (pinfunction "A_A") (pintype "passive"))
      (node (ref "R42") (pin "1") (pinfunction "1_1") (pintype "passive"))
    )
    (net (code "75") (name "Net-(LED6-PadA)") (class "Default")
      (node (ref "LED6") (pin "A") (pinfunction "A_A") (pintype "passive"))
      (node (ref "R43") (pin "1") (pinfunction "1_1") (pintype "passive"))
    )
    (net (code "76") (name "Net-(R41-Pad2)") (class "Default")
      (node (ref "R41") (pin "2") (pinfunction "2_2") (pintype "passive"))
      (node (ref "U$1") (pin "D10") (pinfunction "D10_D10") (pintype "bidirectional"))
    )
    (net (code "77") (name "Net-(R42-Pad2)") (class "Default")
      (node (ref "R42") (pin "2") (pinfunction "2_2") (pintype "passive"))
      (node (ref "U$1") (pin "D11") (pinfunction "D11_D11") (pintype "bidirectional"))
    )
    (net (code "78") (name "Net-(R43-Pad2)") (class "Default")
      (node (ref "R43") (pin "2") (pinfunction "2_2") (pintype "passive"))
      (node (ref "U$1") (pin "D12") (pinfunction "D12_D12") (pintype "bidirectional"))
    )
    (net (code "79") (name "unconnected-(DIS1-DB0-Pad7)") (class "Default")
      (node (ref "DIS1") (pin "7") (pinfunction "DB0_7") (pintype "bidirectional"))
    )
    (net (code "80") (name "unconnected-(DIS1-DB1-Pad8)") (class "Default")
      (node (ref "DIS1") (pin "8") (pinfunction "DB1_8") (pintype "bidirectional"))
    )
    (net (code "81") (name "unconnected-(DIS1-DB2-Pad9)") (class "Default")
      (node (ref "DIS1") (pin "9") (pinfunction "DB2_9") (pintype "bidirectional"))
    )
    (net (code "82") (name "unconnected-(DIS1-DB3-Pad10)") (class "Default")
      (node (ref "DIS1") (pin "10") (pinfunction "DB3_10") (pintype "bidirectional"))
    )
    (net (code "83") (name "unconnected-(JP2-Pad2)") (class "Default")
      (node (ref "JP2") (pin "2") (pinfunction "2_2") (pintype "passive"))
    )
    (net (code "84") (name "unconnected-(JP2-Pad3)") (class "Default")
      (node (ref "JP2") (pin "3") (pinfunction "3_3") (pintype "passive"))
    )
    (net (code "85") (name "unconnected-(JP2-Pad5)") (class "Default")
      (node (ref "JP2") (pin "5") (pinfunction "5_5") (pintype "passive"))
    )
    (net (code "86") (name "unconnected-(JP2-Pad7)") (class "Default")
      (node (ref "JP2") (pin "7") (pinfunction "7_7") (pintype "passive"))
    )
    (net (code "87") (name "unconnected-(JP2-Pad9)") (class "Default")
      (node (ref "JP2") (pin "9") (pinfunction "9_9") (pintype "passive"))
    )
    (net (code "88") (name "unconnected-(JP2-Pad11)") (class "Default")
      (node (ref "JP2") (pin "11") (pinfunction "11_11") (pintype "passive"))
    )
    (net (code "89") (name "unconnected-(JP2-Pad13)") (class "Default")
      (node (ref "JP2") (pin "13") (pinfunction "13_13") (pintype "passive"))
    )
    (net (code "90") (name "unconnected-(JP2-Pad17)") (class "Default")
      (node (ref "JP2") (pin "17") (pinfunction "17_17") (pintype "passive"))
    )
    (net (code "91") (name "unconnected-(JP2-Pad19)") (class "Default")
      (node (ref "JP2") (pin "19") (pinfunction "19_19") (pintype "passive"))
    )
    (net (code "92") (name "unconnected-(JP2-Pad21)") (class "Default")
      (node (ref "JP2") (pin "21") (pinfunction "21_21") (pintype "passive"))
    )
    (net (code "93") (name "unconnected-(JP2-Pad25)") (class "Default")
      (node (ref "JP2") (pin "25") (pinfunction "25_25") (pintype "passive"))
    )
    (net (code "94") (name "unconnected-(JP2-Pad27)") (class "Default")
      (node (ref "JP2") (pin "27") (pinfunction "27_27") (pintype "passive"))
    )
    (net (code "95") (name "unconnected-(JP2-Pad29)") (class "Default")
      (node (ref "JP2") (pin "29") (pinfunction "29_29") (pintype "passive"))
    )
    (net (code "96") (name "unconnected-(JP2-Pad33)") (class "Default")
      (node (ref "JP2") (pin "33") (pinfunction "33_33") (pintype "passive"))
    )
    (net (code "97") (name "unconnected-(JP4-Pad1)") (class "Default")
      (node (ref "JP4") (pin "1") (pinfunction "1_1") (pintype "passive"))
    )
    (net (code "98") (name "unconnected-(JP4-Pad6)") (class "Default")
      (node (ref "JP4") (pin "6") (pinfunction "6_6") (pintype "passive"))
    )
    (net (code "99") (name "unconnected-(U$1-+3V3.1-Pad3V3.1)") (class "Default")
      (node (ref "U$1") (pin "3V3.1") (pinfunction "+3V3.1_3V3.1") (pintype "bidirectional"))
    )
    (net (code "100") (name "unconnected-(U$1-+3V3.2-Pad3V3.2)") (class "Default")
      (node (ref "U$1") (pin "3V3.2") (pinfunction "+3V3.2_3V3.2") (pintype "bidirectional"))
    )
    (net (code "101") (name "unconnected-(U$1-AREF-PadAREF.1)") (class "Default")
      (node (ref "U$1") (pin "AREF.1") (pinfunction "AREF_AREF.1") (pintype "bidirectional"))
    )
    (net (code "102") (name "unconnected-(U$1-PadA0)") (class "Default")
      (node (ref "U$1") (pin "A0") (pinfunction "A0_A0") (pintype "bidirectional"))
    )
    (net (code "103") (name "unconnected-(U$1-PadA1)") (class "Default")
      (node (ref "U$1") (pin "A1") (pinfunction "A1_A1") (pintype "bidirectional"))
    )
    (net (code "104") (name "unconnected-(U$1-PadA2)") (class "Default")
      (node (ref "U$1") (pin "A2") (pinfunction "A2_A2") (pintype "bidirectional"))
    )
    (net (code "105") (name "unconnected-(U$1-PadA3)") (class "Default")
      (node (ref "U$1") (pin "A3") (pinfunction "A3_A3") (pintype "bidirectional"))
    )
    (net (code "106") (name "unconnected-(U$1-PadA4)") (class "Default")
      (node (ref "U$1") (pin "A4") (pinfunction "A4_A4") (pintype "bidirectional"))
    )
    (net (code "107") (name "unconnected-(U$1-PadA5)") (class "Default")
      (node (ref "U$1") (pin "A5") (pinfunction "A5_A5") (pintype "bidirectional"))
    )
    (net (code "108") (name "unconnected-(U$1-PadA6)") (class "Default")
      (node (ref "U$1") (pin "A6") (pinfunction "A6_A6") (pintype "bidirectional"))
    )
    (net (code "109") (name "unconnected-(U$1-PadA7)") (class "Default")
      (node (ref "U$1") (pin "A7") (pinfunction "A7_A7") (pintype "bidirectional"))
    )
    (net (code "110") (name "unconnected-(U$1-PadA8)") (class "Default")
      (node (ref "U$1") (pin "A8") (pinfunction "A8_A8") (pintype "bidirectional"))
    )
    (net (code "111") (name "unconnected-(U$1-PadA9)") (class "Default")
      (node (ref "U$1") (pin "A9") (pinfunction "A9_A9") (pintype "bidirectional"))
    )
    (net (code "112") (name "unconnected-(U$1-PadA10)") (class "Default")
      (node (ref "U$1") (pin "A10") (pinfunction "A10_A10") (pintype "bidirectional"))
    )
    (net (code "113") (name "unconnected-(U$1-PadA11)") (class "Default")
      (node (ref "U$1") (pin "A11") (pinfunction "A11_A11") (pintype "bidirectional"))
    )
    (net (code "114") (name "unconnected-(U$1-PadA12)") (class "Default")
      (node (ref "U$1") (pin "A12") (pinfunction "A12_A12") (pintype "bidirectional"))
    )
    (net (code "115") (name "unconnected-(U$1-PadA13)") (class "Default")
      (node (ref "U$1") (pin "A13") (pinfunction "A13_A13") (pintype "bidirectional"))
    )
    (net (code "116") (name "unconnected-(U$1-PadD13)") (class "Default")
      (node (ref "U$1") (pin "D13") (pinfunction "D13_D13") (pintype "bidirectional"))
    )
    (net (code "117") (name "unconnected-(U$1-PadD18)") (class "Default")
      (node (ref "U$1") (pin "D18") (pinfunction "D18_D18") (pintype "bidirectional"))
    )
    (net (code "118") (name "unconnected-(U$1-PadD19)") (class "Default")
      (node (ref "U$1") (pin "D19") (pinfunction "D19_D19") (pintype "bidirectional"))
    )
    (net (code "119") (name "unconnected-(U$1-PadRST)") (class "Default")
      (node (ref "U$1") (pin "RST") (pinfunction "RST_RST") (pintype "bidirectional"))
    )
    (net (code "120") (name "unconnected-(U$1-PadRX)") (class "Default")
      (node (ref "U$1") (pin "RX") (pinfunction "RX_RX") (pintype "bidirectional"))
    )
    (net (code "121") (name "unconnected-(U$1-PadTX)") (class "Default")
      (node (ref "U$1") (pin "TX") (pinfunction "TX_TX") (pintype "bidirectional"))
    )
    (net (code "122") (name "unconnected-(U$1-PadVIN.1)") (class "Default")
      (node (ref "U$1") (pin "VIN.1") (pinfunction "VIN.1_VIN.1") (pintype "bidirectional"))
    )
    (net (code "123") (name "unconnected-(U$1-PadVIN.2)") (class "Default")
      (node (ref "U$1") (pin "VIN.2") (pinfunction "VIN.2_VIN.2") (pintype "bidirectional"))
    )
    (net (code "124") (name "unconnected-(U$2-P$1-Pad3V0)") (class "Default")
      (node (ref "U$2") (pin "3V0") (pinfunction "P$1_3V0") (pintype "bidirectional"))
    )
    (net (code "125") (name "unconnected-(U$2-P$2-PadADR)") (class "Default")
      (node (ref "U$2") (pin "ADR") (pinfunction "P$2_ADR") (pintype "bidirectional"))
    )
    (net (code "126") (name "unconnected-(U$2-P$4-PadINT)") (class "Default")
      (node (ref "U$2") (pin "INT") (pinfunction "P$4_INT") (pintype "bidirectional"))
    )
    (net (code "127") (name "unconnected-(U$2-P$5-PadPS0)") (class "Default")
      (node (ref "U$2") (pin "PS0") (pinfunction "P$5_PS0") (pintype "bidirectional"))
    )
    (net (code "128") (name "unconnected-(U$2-P$6-PadPS1)") (class "Default")
      (node (ref "U$2") (pin "PS1") (pinfunction "P$6_PS1") (pintype "bidirectional"))
    )
    (net (code "129") (name "unconnected-(U$2-P$7-PadRST)") (class "Default")
      (node (ref "U$2") (pin "RST") (pinfunction "P$7_RST") (pintype "bidirectional"))
    )
  )
)
